# beaconboard.net
KiCad netlist of a schematic drawn in EAGLE
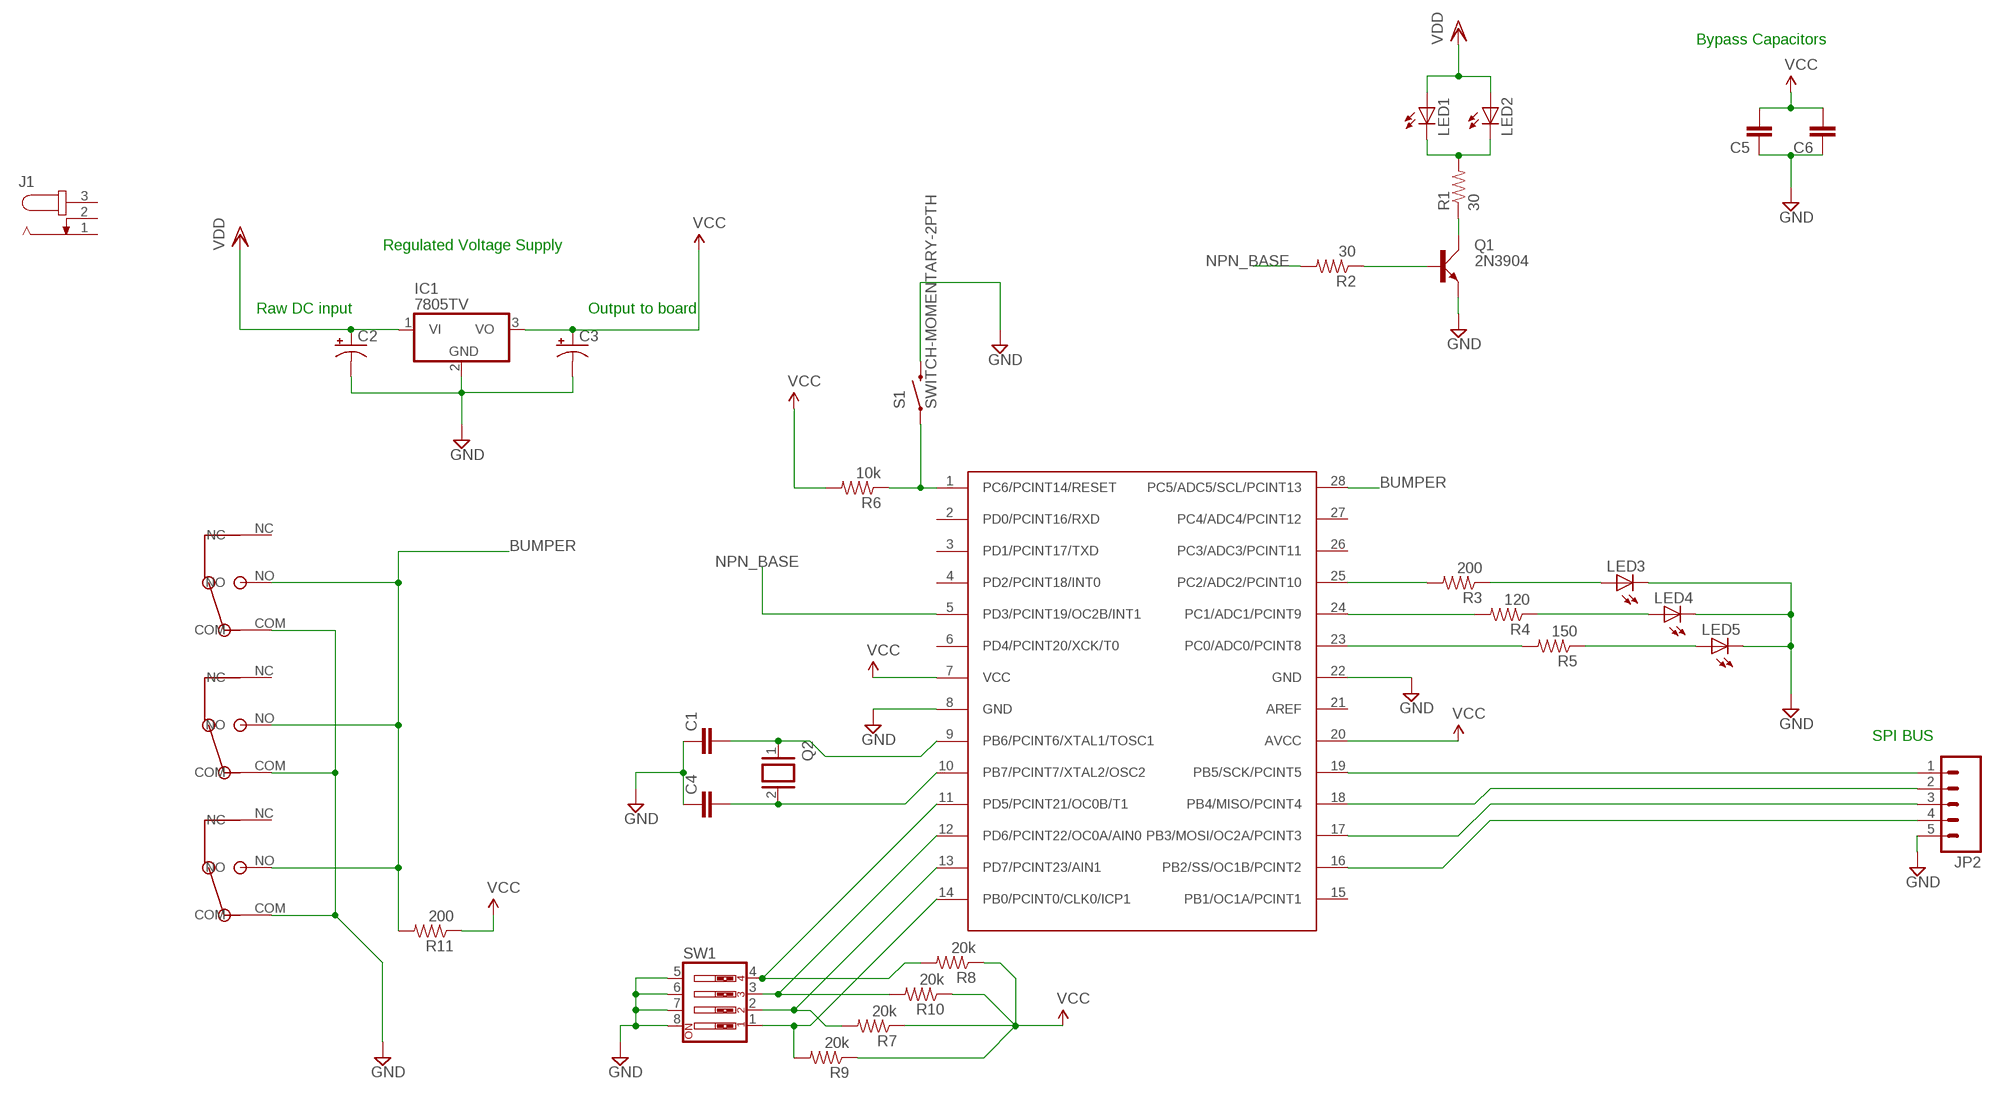
[diagram p0: schematic, sheet 1]

(export (version "E")
  (design (tool "Eeschema 10.0.6"))
  (components
    (comp (ref "C1")
      (value "CAPPTH")
      (footprint "eagle-import:CAP-PTH-SMALL")
      (libsource (lib "eagle-import") (part "CAPPTH"))
    )
    (comp (ref "C2")
      (value "CAP_POLPTH2")
      (footprint "eagle-import:CPOL-RADIAL-10UF-25V")
      (libsource (lib "eagle-import") (part "CAP_POLPTH2"))
    )
    (comp (ref "C3")
      (value "CAP_POLPTH2")
      (footprint "eagle-import:CPOL-RADIAL-10UF-25V")
      (libsource (lib "eagle-import") (part "CAP_POLPTH2"))
    )
    (comp (ref "C4")
      (value "CAPPTH")
      (footprint "eagle-import:CAP-PTH-SMALL")
      (libsource (lib "eagle-import") (part "CAPPTH"))
    )
    (comp (ref "C5")
      (value "CAPPTH")
      (footprint "eagle-import:CAP-PTH-SMALL")
      (libsource (lib "eagle-import") (part "CAPPTH"))
    )
    (comp (ref "C6")
      (value "CAPPTH")
      (footprint "eagle-import:CAP-PTH-SMALL")
      (libsource (lib "eagle-import") (part "CAPPTH"))
    )
    (comp (ref "IC1")
      (value "7805TV")
      (footprint "eagle-import:TO220V")
      (libsource (lib "eagle-import") (part "78TV05"))
    )
    (comp (ref "J1")
      (value "JACK-PLUG1")
      (footprint "eagle-import:SPC4078")
      (libsource (lib "eagle-import") (part "JACK-PLUG1"))
    )
    (comp (ref "JP2")
      (value "M05LOCK_LONGPADS")
      (footprint "eagle-import:1X05_LOCK_LONGPADS")
      (libsource (lib "eagle-import") (part "M05LOCK_LONGPADS"))
    )
    (comp (ref "LED1")
      (value "LED-2AC-CP41B-WES")
      (footprint "eagle-import:CP41B")
      (libsource (lib "eagle-import") (part "LED-2AC-CP41B-WES"))
    )
    (comp (ref "LED2")
      (value "LED-2AC-CP41B-WES")
      (footprint "eagle-import:CP41B")
      (libsource (lib "eagle-import") (part "LED-2AC-CP41B-WES"))
    )
    (comp (ref "LED3")
      (value "LED5MM")
      (footprint "eagle-import:LED5MM")
      (libsource (lib "eagle-import") (part "LED5MM"))
    )
    (comp (ref "LED4")
      (value "LED5MM")
      (footprint "eagle-import:LED5MM")
      (libsource (lib "eagle-import") (part "LED5MM"))
    )
    (comp (ref "LED5")
      (value "LED5MM")
      (footprint "eagle-import:LED5MM")
      (libsource (lib "eagle-import") (part "LED5MM"))
    )
    (comp (ref "Q1")
      (value "2N3904")
      (footprint "eagle-import:TO92D")
      (libsource (lib "eagle-import") (part "2N3904"))
    )
    (comp (ref "Q2")
      (value "XTAL/S")
      (footprint "eagle-import:QS")
      (libsource (lib "eagle-import") (part "XTAL/S"))
    )
    (comp (ref "R1")
      (value "30")
      (footprint "eagle-import:AXIAL-0.4")
      (libsource (lib "eagle-import") (part "RESISTORPTH-1/4W"))
    )
    (comp (ref "R2")
      (value "30")
      (footprint "eagle-import:AXIAL-0.4")
      (libsource (lib "eagle-import") (part "RESISTORPTH-1/4W"))
    )
    (comp (ref "R3")
      (value "200")
      (footprint "eagle-import:AXIAL-0.4")
      (libsource (lib "eagle-import") (part "RESISTORPTH-1/4W"))
    )
    (comp (ref "R4")
      (value "120")
      (footprint "eagle-import:AXIAL-0.4")
      (libsource (lib "eagle-import") (part "RESISTORPTH-1/4W"))
    )
    (comp (ref "R5")
      (value "150")
      (footprint "eagle-import:AXIAL-0.4")
      (libsource (lib "eagle-import") (part "RESISTORPTH-1/4W"))
    )
    (comp (ref "R6")
      (value "10k")
      (footprint "eagle-import:AXIAL-0.4")
      (libsource (lib "eagle-import") (part "RESISTORPTH-1/4W"))
    )
    (comp (ref "R7")
      (value "20k")
      (footprint "eagle-import:AXIAL-0.4")
      (libsource (lib "eagle-import") (part "RESISTORPTH-1/4W"))
    )
    (comp (ref "R8")
      (value "20k")
      (footprint "eagle-import:AXIAL-0.4")
      (libsource (lib "eagle-import") (part "RESISTORPTH-1/4W"))
    )
    (comp (ref "R9")
      (value "20k")
      (footprint "eagle-import:AXIAL-0.4")
      (libsource (lib "eagle-import") (part "RESISTORPTH-1/4W"))
    )
    (comp (ref "R10")
      (value "20k")
      (footprint "eagle-import:AXIAL-0.4")
      (libsource (lib "eagle-import") (part "RESISTORPTH-1/4W"))
    )
    (comp (ref "R11")
      (value "200")
      (footprint "eagle-import:AXIAL-0.4")
      (libsource (lib "eagle-import") (part "RESISTORPTH-1/4W"))
    )
    (comp (ref "S1")
      (value "SWITCH-MOMENTARY-2PTH")
      (footprint "eagle-import:TACTILE-PTH")
      (libsource (lib "eagle-import") (part "SWITCH-MOMENTARY-2PTH"))
    )
    (comp (ref "SW1")
      (value "SW_DIP-4")
      (footprint "eagle-import:EDG-04")
      (libsource (lib "eagle-import") (part "SW_DIP-4"))
    )
    (comp (ref "U$1")
      (value "DF2-L")
      (footprint "eagle-import:D2F-L")
      (libsource (lib "eagle-import") (part "DF2-L"))
    )
    (comp (ref "U$2")
      (value "DF2-L")
      (footprint "eagle-import:D2F-L")
      (libsource (lib "eagle-import") (part "DF2-L"))
    )
    (comp (ref "U$3")
      (value "DF2-L")
      (footprint "eagle-import:D2F-L")
      (libsource (lib "eagle-import") (part "DF2-L"))
    )
    (comp (ref "U$4")
      (value "ATMEGA328")
      (footprint "eagle-import:DIL28-3")
      (libsource (lib "eagle-import") (part "ATMEGA328"))
    )
  )
  (nets
    (net (code "1") (name "/BUMPER") (class "Default")
      (node (ref "R11") (pin "P$2") (pinfunction "2_P$2") (pintype "passive"))
      (node (ref "U$1") (pin "NO") (pinfunction "NO_NO") (pintype "bidirectional"))
      (node (ref "U$2") (pin "NO") (pinfunction "NO_NO") (pintype "bidirectional"))
      (node (ref "U$3") (pin "NO") (pinfunction "NO_NO") (pintype "bidirectional"))
      (node (ref "U$4") (pin "28") (pinfunction "PC5/ADC5/SCL/PCINT13_28") (pintype "bidirectional"))
    )
    (net (code "2") (name "/NPN_BASE") (class "Default")
      (node (ref "R2") (pin "P$2") (pinfunction "2_P$2") (pintype "passive"))
      (node (ref "U$4") (pin "5") (pinfunction "PD3/PCINT19/OC2B/INT1_5") (pintype "bidirectional"))
    )
    (net (code "3") (name "GND") (class "Default")
      (node (ref "C1") (pin "1") (pinfunction "1_1") (pintype "passive"))
      (node (ref "C2") (pin "2") (pinfunction "-_2") (pintype "passive"))
      (node (ref "C3") (pin "2") (pinfunction "-_2") (pintype "passive"))
      (node (ref "C4") (pin "1") (pinfunction "1_1") (pintype "passive"))
      (node (ref "C5") (pin "1") (pinfunction "1_1") (pintype "passive"))
      (node (ref "C6") (pin "1") (pinfunction "1_1") (pintype "passive"))
      (node (ref "IC1") (pin "2") (pinfunction "GND_2") (pintype "passive"))
      (node (ref "JP2") (pin "5") (pinfunction "5_5") (pintype "passive"))
      (node (ref "LED3") (pin "K") (pinfunction "C_K") (pintype "passive"))
      (node (ref "LED4") (pin "K") (pinfunction "C_K") (pintype "passive"))
      (node (ref "LED5") (pin "K") (pinfunction "C_K") (pintype "passive"))
      (node (ref "Q1") (pin "E") (pinfunction "E_E") (pintype "passive"))
      (node (ref "S1") (pin "3") (pinfunction "2_3") (pintype "passive"))
      (node (ref "SW1") (pin "5") (pinfunction "5_5") (pintype "passive"))
      (node (ref "SW1") (pin "6") (pinfunction "6_6") (pintype "passive"))
      (node (ref "SW1") (pin "7") (pinfunction "7_7") (pintype "passive"))
      (node (ref "SW1") (pin "8") (pinfunction "8_8") (pintype "passive"))
      (node (ref "U$1") (pin "COM") (pinfunction "COM_COM") (pintype "bidirectional"))
      (node (ref "U$2") (pin "COM") (pinfunction "COM_COM") (pintype "bidirectional"))
      (node (ref "U$3") (pin "COM") (pinfunction "COM_COM") (pintype "bidirectional"))
      (node (ref "U$4") (pin "22") (pinfunction "GND_22") (pintype "power_in"))
      (node (ref "U$4") (pin "8") (pinfunction "GND_8") (pintype "power_in"))
    )
    (net (code "4") (name "Net-(R1-1)") (class "Default")
      (node (ref "Q1") (pin "C") (pinfunction "C_C") (pintype "passive"))
      (node (ref "R1") (pin "P$1") (pinfunction "1_P$1") (pintype "passive"))
    )
    (net (code "5") (name "Net-(R1-2)") (class "Default")
      (node (ref "LED1") (pin "1") (pinfunction "C_1") (pintype "passive"))
      (node (ref "LED1") (pin "4") (pinfunction "C_4") (pintype "passive"))
      (node (ref "LED2") (pin "1") (pinfunction "C_1") (pintype "passive"))
      (node (ref "LED2") (pin "4") (pinfunction "C_4") (pintype "passive"))
      (node (ref "R1") (pin "P$2") (pinfunction "2_P$2") (pintype "passive"))
    )
    (net (code "6") (name "Net-(R2-1)") (class "Default")
      (node (ref "Q1") (pin "B") (pinfunction "B_B") (pintype "passive"))
      (node (ref "R2") (pin "P$1") (pinfunction "1_P$1") (pintype "passive"))
    )
    (net (code "7") (name "Net-(R3-1)") (class "Default")
      (node (ref "LED3") (pin "A") (pinfunction "A_A") (pintype "passive"))
      (node (ref "R3") (pin "P$1") (pinfunction "1_P$1") (pintype "passive"))
    )
    (net (code "8") (name "Net-(R3-2)") (class "Default")
      (node (ref "R3") (pin "P$2") (pinfunction "2_P$2") (pintype "passive"))
      (node (ref "U$4") (pin "25") (pinfunction "PC2/ADC2/PCINT10_25") (pintype "bidirectional"))
    )
    (net (code "9") (name "Net-(R4-1)") (class "Default")
      (node (ref "LED4") (pin "A") (pinfunction "A_A") (pintype "passive"))
      (node (ref "R4") (pin "P$1") (pinfunction "1_P$1") (pintype "passive"))
    )
    (net (code "10") (name "Net-(R4-2)") (class "Default")
      (node (ref "R4") (pin "P$2") (pinfunction "2_P$2") (pintype "passive"))
      (node (ref "U$4") (pin "24") (pinfunction "PC1/ADC1/PCINT9_24") (pintype "bidirectional"))
    )
    (net (code "11") (name "Net-(R5-1)") (class "Default")
      (node (ref "LED5") (pin "A") (pinfunction "A_A") (pintype "passive"))
      (node (ref "R5") (pin "P$1") (pinfunction "1_P$1") (pintype "passive"))
    )
    (net (code "12") (name "Net-(R5-2)") (class "Default")
      (node (ref "R5") (pin "P$2") (pinfunction "2_P$2") (pintype "passive"))
      (node (ref "U$4") (pin "23") (pinfunction "PC0/ADC0/PCINT8_23") (pintype "bidirectional"))
    )
    (net (code "13") (name "Net-(R6-1)") (class "Default")
      (node (ref "R6") (pin "P$1") (pinfunction "1_P$1") (pintype "passive"))
      (node (ref "S1") (pin "1") (pinfunction "1_1") (pintype "passive"))
      (node (ref "U$4") (pin "1") (pinfunction "PC6/PCINT14/RESET_1") (pintype "bidirectional"))
    )
    (net (code "14") (name "Net-(R7-2)") (class "Default")
      (node (ref "R7") (pin "P$2") (pinfunction "2_P$2") (pintype "passive"))
      (node (ref "SW1") (pin "2") (pinfunction "2_2") (pintype "passive"))
      (node (ref "U$4") (pin "13") (pinfunction "PD7/PCINT23/AIN1_13") (pintype "bidirectional"))
    )
    (net (code "15") (name "Net-(R8-2)") (class "Default")
      (node (ref "R8") (pin "P$2") (pinfunction "2_P$2") (pintype "passive"))
      (node (ref "SW1") (pin "4") (pinfunction "4_4") (pintype "passive"))
      (node (ref "U$4") (pin "11") (pinfunction "PD5/PCINT21/OC0B/T1_11") (pintype "bidirectional"))
    )
    (net (code "16") (name "Net-(R9-2)") (class "Default")
      (node (ref "R9") (pin "P$2") (pinfunction "2_P$2") (pintype "passive"))
      (node (ref "SW1") (pin "1") (pinfunction "1_1") (pintype "passive"))
      (node (ref "U$4") (pin "14") (pinfunction "PB0/PCINT0/CLK0/ICP1_14") (pintype "bidirectional"))
    )
    (net (code "17") (name "Net-(R10-2)") (class "Default")
      (node (ref "R10") (pin "P$2") (pinfunction "2_P$2") (pintype "passive"))
      (node (ref "SW1") (pin "3") (pinfunction "3_3") (pintype "passive"))
      (node (ref "U$4") (pin "12") (pinfunction "PD6/PCINT22/OC0A/AIN0_12") (pintype "bidirectional"))
    )
    (net (code "18") (name "Net-(U$4-PB2{slash}SS{slash}OC1B{slash}PCINT2)") (class "Default")
      (node (ref "JP2") (pin "4") (pinfunction "4_4") (pintype "passive"))
      (node (ref "U$4") (pin "16") (pinfunction "PB2/SS/OC1B/PCINT2_16") (pintype "bidirectional"))
    )
    (net (code "19") (name "Net-(U$4-PB3{slash}MOSI{slash}OC2A{slash}PCINT3)") (class "Default")
      (node (ref "JP2") (pin "3") (pinfunction "3_3") (pintype "passive"))
      (node (ref "U$4") (pin "17") (pinfunction "PB3/MOSI/OC2A/PCINT3_17") (pintype "bidirectional"))
    )
    (net (code "20") (name "Net-(U$4-PB4{slash}MISO{slash}PCINT4)") (class "Default")
      (node (ref "JP2") (pin "2") (pinfunction "2_2") (pintype "passive"))
      (node (ref "U$4") (pin "18") (pinfunction "PB4/MISO/PCINT4_18") (pintype "bidirectional"))
    )
    (net (code "21") (name "Net-(U$4-PB5{slash}SCK{slash}PCINT5)") (class "Default")
      (node (ref "JP2") (pin "1") (pinfunction "1_1") (pintype "passive"))
      (node (ref "U$4") (pin "19") (pinfunction "PB5/SCK/PCINT5_19") (pintype "bidirectional"))
    )
    (net (code "22") (name "Net-(U$4-PB6{slash}PCINT6{slash}XTAL1{slash}TOSC1)") (class "Default")
      (node (ref "C1") (pin "2") (pinfunction "2_2") (pintype "passive"))
      (node (ref "Q2") (pin "1") (pinfunction "1_1") (pintype "passive"))
      (node (ref "U$4") (pin "9") (pinfunction "PB6/PCINT6/XTAL1/TOSC1_9") (pintype "bidirectional"))
    )
    (net (code "23") (name "Net-(U$4-PB7{slash}PCINT7{slash}XTAL2{slash}OSC2)") (class "Default")
      (node (ref "C4") (pin "2") (pinfunction "2_2") (pintype "passive"))
      (node (ref "Q2") (pin "2") (pinfunction "2_2") (pintype "passive"))
      (node (ref "U$4") (pin "10") (pinfunction "PB7/PCINT7/XTAL2/OSC2_10") (pintype "bidirectional"))
    )
    (net (code "24") (name "VCC") (class "Default")
      (node (ref "C3") (pin "1") (pinfunction "+_1") (pintype "passive"))
      (node (ref "C5") (pin "2") (pinfunction "2_2") (pintype "passive"))
      (node (ref "C6") (pin "2") (pinfunction "2_2") (pintype "passive"))
      (node (ref "IC1") (pin "3") (pinfunction "VO_3") (pintype "passive"))
      (node (ref "R10") (pin "P$1") (pinfunction "1_P$1") (pintype "passive"))
      (node (ref "R11") (pin "P$1") (pinfunction "1_P$1") (pintype "passive"))
      (node (ref "R6") (pin "P$2") (pinfunction "2_P$2") (pintype "passive"))
      (node (ref "R7") (pin "P$1") (pinfunction "1_P$1") (pintype "passive"))
      (node (ref "R8") (pin "P$1") (pinfunction "1_P$1") (pintype "passive"))
      (node (ref "R9") (pin "P$1") (pinfunction "1_P$1") (pintype "passive"))
      (node (ref "U$4") (pin "20") (pinfunction "AVCC_20") (pintype "bidirectional"))
      (node (ref "U$4") (pin "7") (pinfunction "VCC_7") (pintype "power_in"))
    )
    (net (code "25") (name "VDD") (class "Default")
      (node (ref "C2") (pin "1") (pinfunction "+_1") (pintype "passive"))
      (node (ref "IC1") (pin "1") (pinfunction "VI_1") (pintype "input"))
      (node (ref "LED1") (pin "2") (pinfunction "A_2") (pintype "passive"))
      (node (ref "LED1") (pin "3") (pinfunction "A_3") (pintype "passive"))
      (node (ref "LED2") (pin "2") (pinfunction "A_2") (pintype "passive"))
      (node (ref "LED2") (pin "3") (pinfunction "A_3") (pintype "passive"))
    )
    (net (code "26") (name "unconnected-(J1-Pad1)") (class "Default")
      (node (ref "J1") (pin "1") (pinfunction "1_1") (pintype "passive"))
    )
    (net (code "27") (name "unconnected-(J1-Pad2)") (class "Default")
      (node (ref "J1") (pin "2") (pinfunction "2_2") (pintype "passive"))
    )
    (net (code "28") (name "unconnected-(J1-Pad3)") (class "Default")
      (node (ref "J1") (pin "3") (pinfunction "3_3") (pintype "passive"))
    )
    (net (code "29") (name "unconnected-(U$1-PadNC)") (class "Default")
      (node (ref "U$1") (pin "NC") (pinfunction "NC_NC") (pintype "bidirectional"))
    )
    (net (code "30") (name "unconnected-(U$2-PadNC)") (class "Default")
      (node (ref "U$2") (pin "NC") (pinfunction "NC_NC") (pintype "bidirectional"))
    )
    (net (code "31") (name "unconnected-(U$3-PadNC)") (class "Default")
      (node (ref "U$3") (pin "NC") (pinfunction "NC_NC") (pintype "bidirectional"))
    )
    (net (code "32") (name "unconnected-(U$4-AREF-Pad21)") (class "Default")
      (node (ref "U$4") (pin "21") (pinfunction "AREF_21") (pintype "bidirectional"))
    )
    (net (code "33") (name "unconnected-(U$4-PB1{slash}OC1A{slash}PCINT1-Pad15)") (class "Default")
      (node (ref "U$4") (pin "15") (pinfunction "PB1/OC1A/PCINT1_15") (pintype "bidirectional"))
    )
    (net (code "34") (name "unconnected-(U$4-PC3{slash}ADC3{slash}PCINT11-Pad26)") (class "Default")
      (node (ref "U$4") (pin "26") (pinfunction "PC3/ADC3/PCINT11_26") (pintype "bidirectional"))
    )
    (net (code "35") (name "unconnected-(U$4-PC4{slash}ADC4{slash}PCINT12-Pad27)") (class "Default")
      (node (ref "U$4") (pin "27") (pinfunction "PC4/ADC4/PCINT12_27") (pintype "bidirectional"))
    )
    (net (code "36") (name "unconnected-(U$4-PD0{slash}PCINT16{slash}RXD-Pad2)") (class "Default")
      (node (ref "U$4") (pin "2") (pinfunction "PD0/PCINT16/RXD_2") (pintype "bidirectional"))
    )
    (net (code "37") (name "unconnected-(U$4-PD1{slash}PCINT17{slash}TXD-Pad3)") (class "Default")
      (node (ref "U$4") (pin "3") (pinfunction "PD1/PCINT17/TXD_3") (pintype "bidirectional"))
    )
    (net (code "38") (name "unconnected-(U$4-PD2{slash}PCINT18{slash}INT0-Pad4)") (class "Default")
      (node (ref "U$4") (pin "4") (pinfunction "PD2/PCINT18/INT0_4") (pintype "bidirectional"))
    )
    (net (code "39") (name "unconnected-(U$4-PD4{slash}PCINT20{slash}XCK{slash}T0-Pad6)") (class "Default")
      (node (ref "U$4") (pin "6") (pinfunction "PD4/PCINT20/XCK/T0_6") (pintype "bidirectional"))
    )
  )
)
